# TEENSY_4.net
KiCad netlist of a schematic drawn in Altium Designer
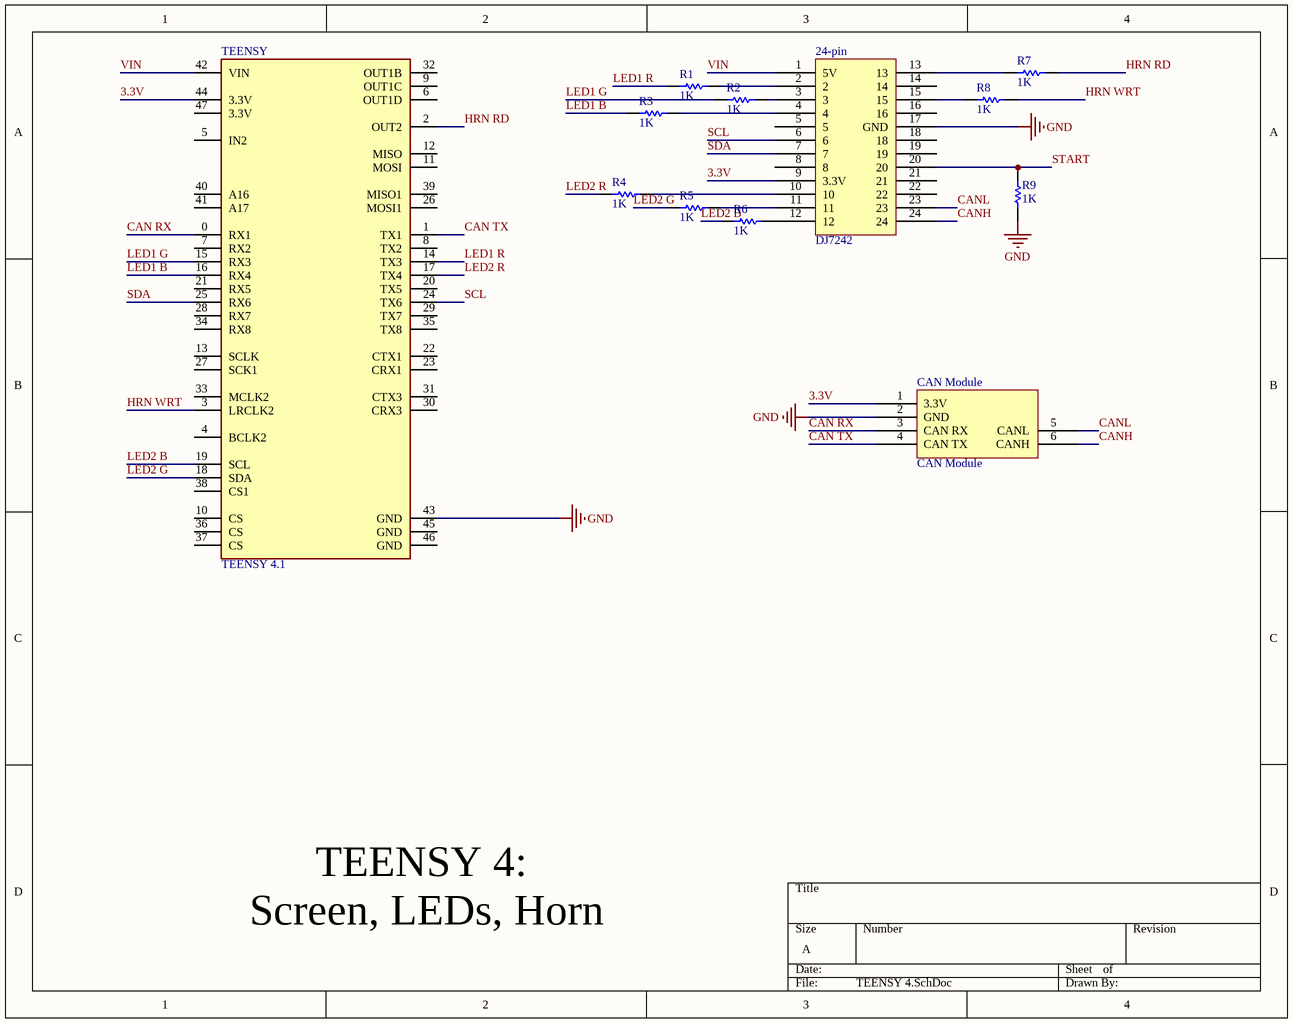
[diagram p0: TEENSY 4.SchDoc]

(export (version "E")
  (design (tool "Eeschema 10.0.6"))
  (components
    (comp (ref "24-pin")
      (value "DJ7242")
      (footprint "DJ7242-Footprint-1")
      (description "24-pin connector")
      (libsource (lib "cmabey15") (part "DJ7242-Symbol-1"))
    )
    (comp (ref "CAN Module")
      (value "CAN Module")
      (footprint "CAN Module-Footprint-1")
      (description "CAN waveshare")
      (libsource (lib "cmabey15") (part "CAN Module-Symbol-1"))
    )
    (comp (ref "R1")
      (value "1K")
      (description "Resistor")
      (libsource (lib "Simulation Generic Components") (part "Resistor"))
    )
    (comp (ref "R2")
      (value "1K")
      (description "Resistor")
      (libsource (lib "Simulation Generic Components") (part "Resistor"))
    )
    (comp (ref "R3")
      (value "1K")
      (description "Resistor")
      (libsource (lib "Simulation Generic Components") (part "Resistor"))
    )
    (comp (ref "R4")
      (value "1K")
      (description "Resistor")
      (libsource (lib "Simulation Generic Components") (part "Resistor"))
    )
    (comp (ref "R5")
      (value "1K")
      (description "Resistor")
      (libsource (lib "Simulation Generic Components") (part "Resistor"))
    )
    (comp (ref "R6")
      (value "1K")
      (description "Resistor")
      (libsource (lib "Simulation Generic Components") (part "Resistor"))
    )
    (comp (ref "R7")
      (value "1K")
      (description "Resistor")
      (libsource (lib "Simulation Generic Components") (part "Resistor"))
    )
    (comp (ref "R8")
      (value "1K")
      (description "Resistor")
      (libsource (lib "Simulation Generic Components") (part "Resistor"))
    )
    (comp (ref "R9")
      (value "1K")
      (description "Resistor")
      (libsource (lib "Simulation Generic Components") (part "Resistor"))
    )
    (comp (ref "TEENSY")
      (value "TEENSY 4.1")
      (footprint "FP-DEV-16996-MFG")
      (description "TEENSY 4.1 (HEADERS)")
      (libsource (lib "Altium Content Vault") (part "080115a1ce54750370cf87ec145ee29"))
    )
  )
  (nets
    (net (code "1") (name "/3.3V") (class "Default")
      (node (ref "24-pin") (pin "9") (pinfunction "3.3V_9") (pintype "passive"))
      (node (ref "CAN Module") (pin "1") (pinfunction "3.3V_1") (pintype "passive"))
      (node (ref "TEENSY") (pin "44") (pinfunction "3.3V_44") (pintype "passive"))
    )
    (net (code "2") (name "/CAN RX") (class "Default")
      (node (ref "CAN Module") (pin "3") (pinfunction "CAN_RX_3") (pintype "passive"))
      (node (ref "TEENSY") (pin "0") (pinfunction "RX1_0") (pintype "passive"))
    )
    (net (code "3") (name "/CAN TX") (class "Default")
      (node (ref "CAN Module") (pin "4") (pinfunction "CAN_TX_4") (pintype "passive"))
      (node (ref "TEENSY") (pin "1") (pinfunction "TX1_1") (pintype "passive"))
    )
    (net (code "4") (name "/CANH") (class "Default")
      (node (ref "24-pin") (pin "24") (pinfunction "24_24") (pintype "passive"))
      (node (ref "CAN Module") (pin "6") (pinfunction "CANH_6") (pintype "passive"))
    )
    (net (code "5") (name "/CANL") (class "Default")
      (node (ref "24-pin") (pin "23") (pinfunction "23_23") (pintype "passive"))
      (node (ref "CAN Module") (pin "5") (pinfunction "CANL_5") (pintype "passive"))
    )
    (net (code "6") (name "/HRN RD") (class "Default")
      (node (ref "R7") (pin "2") (pinfunction "2_2") (pintype "passive"))
      (node (ref "TEENSY") (pin "2") (pinfunction "OUT2_2") (pintype "passive"))
    )
    (net (code "7") (name "/HRN WRT") (class "Default")
      (node (ref "R8") (pin "2") (pinfunction "2_2") (pintype "passive"))
      (node (ref "TEENSY") (pin "3") (pinfunction "LRCLK2_3") (pintype "passive"))
    )
    (net (code "8") (name "/LED1 B") (class "Default")
      (node (ref "R3") (pin "2") (pinfunction "2_2") (pintype "passive"))
      (node (ref "TEENSY") (pin "16") (pinfunction "RX4_16") (pintype "passive"))
    )
    (net (code "9") (name "/LED1 G") (class "Default")
      (node (ref "R2") (pin "2") (pinfunction "2_2") (pintype "passive"))
      (node (ref "TEENSY") (pin "15") (pinfunction "RX3_15") (pintype "passive"))
    )
    (net (code "10") (name "/LED1 R") (class "Default")
      (node (ref "R1") (pin "2") (pinfunction "2_2") (pintype "passive"))
      (node (ref "TEENSY") (pin "14") (pinfunction "TX3_14") (pintype "passive"))
    )
    (net (code "11") (name "/LED2 B") (class "Default")
      (node (ref "R6") (pin "2") (pinfunction "2_2") (pintype "passive"))
      (node (ref "TEENSY") (pin "19") (pinfunction "SCL_19") (pintype "passive"))
    )
    (net (code "12") (name "/LED2 G") (class "Default")
      (node (ref "R5") (pin "2") (pinfunction "2_2") (pintype "passive"))
      (node (ref "TEENSY") (pin "18") (pinfunction "SDA_18") (pintype "passive"))
    )
    (net (code "13") (name "/LED2 R") (class "Default")
      (node (ref "R4") (pin "2") (pinfunction "2_2") (pintype "passive"))
      (node (ref "TEENSY") (pin "17") (pinfunction "TX4_17") (pintype "passive"))
    )
    (net (code "14") (name "/SCL") (class "Default")
      (node (ref "24-pin") (pin "6") (pinfunction "6_6") (pintype "passive"))
      (node (ref "TEENSY") (pin "24") (pinfunction "TX6_24") (pintype "passive"))
    )
    (net (code "15") (name "/SDA") (class "Default")
      (node (ref "24-pin") (pin "7") (pinfunction "7_7") (pintype "passive"))
      (node (ref "TEENSY") (pin "25") (pinfunction "RX6_25") (pintype "passive"))
    )
    (net (code "16") (name "/START") (class "Default")
      (node (ref "24-pin") (pin "20") (pinfunction "20_20") (pintype "passive"))
      (node (ref "R9") (pin "2") (pinfunction "2_2") (pintype "passive"))
    )
    (net (code "17") (name "/VIN") (class "Default")
      (node (ref "24-pin") (pin "1") (pinfunction "5V_1") (pintype "passive"))
      (node (ref "TEENSY") (pin "42") (pinfunction "VIN_42") (pintype "passive"))
    )
    (net (code "18") (name "GND") (class "Default")
      (node (ref "24-pin") (pin "17") (pinfunction "GND_17") (pintype "passive"))
      (node (ref "CAN Module") (pin "2") (pinfunction "GND_2") (pintype "passive"))
      (node (ref "R9") (pin "1") (pinfunction "1_1") (pintype "passive"))
      (node (ref "TEENSY") (pin "43") (pinfunction "GND_43") (pintype "passive"))
    )
    (net (code "19") (name "Net-(24-pin-Pad2)") (class "Default")
      (node (ref "24-pin") (pin "2") (pinfunction "2_2") (pintype "passive"))
      (node (ref "R1") (pin "1") (pinfunction "1_1") (pintype "passive"))
    )
    (net (code "20") (name "Net-(24-pin-Pad3)") (class "Default")
      (node (ref "24-pin") (pin "3") (pinfunction "3_3") (pintype "passive"))
      (node (ref "R2") (pin "1") (pinfunction "1_1") (pintype "passive"))
    )
    (net (code "21") (name "Net-(24-pin-Pad4)") (class "Default")
      (node (ref "24-pin") (pin "4") (pinfunction "4_4") (pintype "passive"))
      (node (ref "R3") (pin "1") (pinfunction "1_1") (pintype "passive"))
    )
    (net (code "22") (name "Net-(24-pin-Pad10)") (class "Default")
      (node (ref "24-pin") (pin "10") (pinfunction "10_10") (pintype "passive"))
      (node (ref "R4") (pin "1") (pinfunction "1_1") (pintype "passive"))
    )
    (net (code "23") (name "Net-(24-pin-Pad11)") (class "Default")
      (node (ref "24-pin") (pin "11") (pinfunction "11_11") (pintype "passive"))
      (node (ref "R5") (pin "1") (pinfunction "1_1") (pintype "passive"))
    )
    (net (code "24") (name "Net-(24-pin-Pad12)") (class "Default")
      (node (ref "24-pin") (pin "12") (pinfunction "12_12") (pintype "passive"))
      (node (ref "R6") (pin "1") (pinfunction "1_1") (pintype "passive"))
    )
    (net (code "25") (name "Net-(24-pin-Pad13)") (class "Default")
      (node (ref "24-pin") (pin "13") (pinfunction "13_13") (pintype "passive"))
      (node (ref "R7") (pin "1") (pinfunction "1_1") (pintype "passive"))
    )
    (net (code "26") (name "Net-(24-pin-Pad15)") (class "Default")
      (node (ref "24-pin") (pin "15") (pinfunction "15_15") (pintype "passive"))
      (node (ref "R8") (pin "1") (pinfunction "1_1") (pintype "passive"))
    )
    (net (code "27") (name "unconnected-(24-pin-Pad5)") (class "Default")
      (node (ref "24-pin") (pin "5") (pinfunction "5_5") (pintype "passive"))
    )
    (net (code "28") (name "unconnected-(24-pin-Pad8)") (class "Default")
      (node (ref "24-pin") (pin "8") (pinfunction "8_8") (pintype "passive"))
    )
    (net (code "29") (name "unconnected-(24-pin-Pad14)") (class "Default")
      (node (ref "24-pin") (pin "14") (pinfunction "14_14") (pintype "passive"))
    )
    (net (code "30") (name "unconnected-(24-pin-Pad16)") (class "Default")
      (node (ref "24-pin") (pin "16") (pinfunction "16_16") (pintype "passive"))
    )
    (net (code "31") (name "unconnected-(24-pin-Pad18)") (class "Default")
      (node (ref "24-pin") (pin "18") (pinfunction "18_18") (pintype "passive"))
    )
    (net (code "32") (name "unconnected-(24-pin-Pad19)") (class "Default")
      (node (ref "24-pin") (pin "19") (pinfunction "19_19") (pintype "passive"))
    )
    (net (code "33") (name "unconnected-(24-pin-Pad21)") (class "Default")
      (node (ref "24-pin") (pin "21") (pinfunction "21_21") (pintype "passive"))
    )
    (net (code "34") (name "unconnected-(24-pin-Pad22)") (class "Default")
      (node (ref "24-pin") (pin "22") (pinfunction "22_22") (pintype "passive"))
    )
    (net (code "35") (name "unconnected-(TEENSY-3.3V-Pad47)") (class "Default")
      (node (ref "TEENSY") (pin "47") (pinfunction "3.3V_47") (pintype "passive"))
    )
    (net (code "36") (name "unconnected-(TEENSY-A16-Pad40)") (class "Default")
      (node (ref "TEENSY") (pin "40") (pinfunction "A16_40") (pintype "passive"))
    )
    (net (code "37") (name "unconnected-(TEENSY-A17-Pad41)") (class "Default")
      (node (ref "TEENSY") (pin "41") (pinfunction "A17_41") (pintype "passive"))
    )
    (net (code "38") (name "unconnected-(TEENSY-BCLK2-Pad4)") (class "Default")
      (node (ref "TEENSY") (pin "4") (pinfunction "BCLK2_4") (pintype "passive"))
    )
    (net (code "39") (name "unconnected-(TEENSY-CRX1-Pad23)") (class "Default")
      (node (ref "TEENSY") (pin "23") (pinfunction "CRX1_23") (pintype "passive"))
    )
    (net (code "40") (name "unconnected-(TEENSY-CRX3-Pad30)") (class "Default")
      (node (ref "TEENSY") (pin "30") (pinfunction "CRX3_30") (pintype "passive"))
    )
    (net (code "41") (name "unconnected-(TEENSY-CS-Pad10)") (class "Default")
      (node (ref "TEENSY") (pin "10") (pinfunction "CS_10") (pintype "passive"))
    )
    (net (code "42") (name "unconnected-(TEENSY-CS-Pad36)") (class "Default")
      (node (ref "TEENSY") (pin "36") (pinfunction "CS_36") (pintype "passive"))
    )
    (net (code "43") (name "unconnected-(TEENSY-CS-Pad37)") (class "Default")
      (node (ref "TEENSY") (pin "37") (pinfunction "CS_37") (pintype "passive"))
    )
    (net (code "44") (name "unconnected-(TEENSY-CS1-Pad38)") (class "Default")
      (node (ref "TEENSY") (pin "38") (pinfunction "CS1_38") (pintype "passive"))
    )
    (net (code "45") (name "unconnected-(TEENSY-CTX1-Pad22)") (class "Default")
      (node (ref "TEENSY") (pin "22") (pinfunction "CTX1_22") (pintype "passive"))
    )
    (net (code "46") (name "unconnected-(TEENSY-CTX3-Pad31)") (class "Default")
      (node (ref "TEENSY") (pin "31") (pinfunction "CTX3_31") (pintype "passive"))
    )
    (net (code "47") (name "unconnected-(TEENSY-GND-Pad45)") (class "Default")
      (node (ref "TEENSY") (pin "45") (pinfunction "GND_45") (pintype "passive"))
    )
    (net (code "48") (name "unconnected-(TEENSY-GND-Pad46)") (class "Default")
      (node (ref "TEENSY") (pin "46") (pinfunction "GND_46") (pintype "passive"))
    )
    (net (code "49") (name "unconnected-(TEENSY-IN2-Pad5)") (class "Default")
      (node (ref "TEENSY") (pin "5") (pinfunction "IN2_5") (pintype "passive"))
    )
    (net (code "50") (name "unconnected-(TEENSY-MCLK2-Pad33)") (class "Default")
      (node (ref "TEENSY") (pin "33") (pinfunction "MCLK2_33") (pintype "passive"))
    )
    (net (code "51") (name "unconnected-(TEENSY-MISO-Pad12)") (class "Default")
      (node (ref "TEENSY") (pin "12") (pinfunction "MISO_12") (pintype "passive"))
    )
    (net (code "52") (name "unconnected-(TEENSY-MISO1-Pad39)") (class "Default")
      (node (ref "TEENSY") (pin "39") (pinfunction "MISO1_39") (pintype "passive"))
    )
    (net (code "53") (name "unconnected-(TEENSY-MOSI-Pad11)") (class "Default")
      (node (ref "TEENSY") (pin "11") (pinfunction "MOSI_11") (pintype "passive"))
    )
    (net (code "54") (name "unconnected-(TEENSY-MOSI1-Pad26)") (class "Default")
      (node (ref "TEENSY") (pin "26") (pinfunction "MOSI1_26") (pintype "passive"))
    )
    (net (code "55") (name "unconnected-(TEENSY-OUT1B-Pad32)") (class "Default")
      (node (ref "TEENSY") (pin "32") (pinfunction "OUT1B_32") (pintype "passive"))
    )
    (net (code "56") (name "unconnected-(TEENSY-OUT1C-Pad9)") (class "Default")
      (node (ref "TEENSY") (pin "9") (pinfunction "OUT1C_9") (pintype "passive"))
    )
    (net (code "57") (name "unconnected-(TEENSY-OUT1D-Pad6)") (class "Default")
      (node (ref "TEENSY") (pin "6") (pinfunction "OUT1D_6") (pintype "passive"))
    )
    (net (code "58") (name "unconnected-(TEENSY-RX2-Pad7)") (class "Default")
      (node (ref "TEENSY") (pin "7") (pinfunction "RX2_7") (pintype "passive"))
    )
    (net (code "59") (name "unconnected-(TEENSY-RX5-Pad21)") (class "Default")
      (node (ref "TEENSY") (pin "21") (pinfunction "RX5_21") (pintype "passive"))
    )
    (net (code "60") (name "unconnected-(TEENSY-RX7-Pad28)") (class "Default")
      (node (ref "TEENSY") (pin "28") (pinfunction "RX7_28") (pintype "passive"))
    )
    (net (code "61") (name "unconnected-(TEENSY-RX8-Pad34)") (class "Default")
      (node (ref "TEENSY") (pin "34") (pinfunction "RX8_34") (pintype "passive"))
    )
    (net (code "62") (name "unconnected-(TEENSY-SCK1-Pad27)") (class "Default")
      (node (ref "TEENSY") (pin "27") (pinfunction "SCK1_27") (pintype "passive"))
    )
    (net (code "63") (name "unconnected-(TEENSY-SCLK-Pad13)") (class "Default")
      (node (ref "TEENSY") (pin "13") (pinfunction "SCLK_13") (pintype "passive"))
    )
    (net (code "64") (name "unconnected-(TEENSY-TX2-Pad8)") (class "Default")
      (node (ref "TEENSY") (pin "8") (pinfunction "TX2_8") (pintype "passive"))
    )
    (net (code "65") (name "unconnected-(TEENSY-TX5-Pad20)") (class "Default")
      (node (ref "TEENSY") (pin "20") (pinfunction "TX5_20") (pintype "passive"))
    )
    (net (code "66") (name "unconnected-(TEENSY-TX7-Pad29)") (class "Default")
      (node (ref "TEENSY") (pin "29") (pinfunction "TX7_29") (pintype "passive"))
    )
    (net (code "67") (name "unconnected-(TEENSY-TX8-Pad35)") (class "Default")
      (node (ref "TEENSY") (pin "35") (pinfunction "TX8_35") (pintype "passive"))
    )
  )
)
